# CAN.net
KiCad netlist of a schematic drawn in Altium Designer
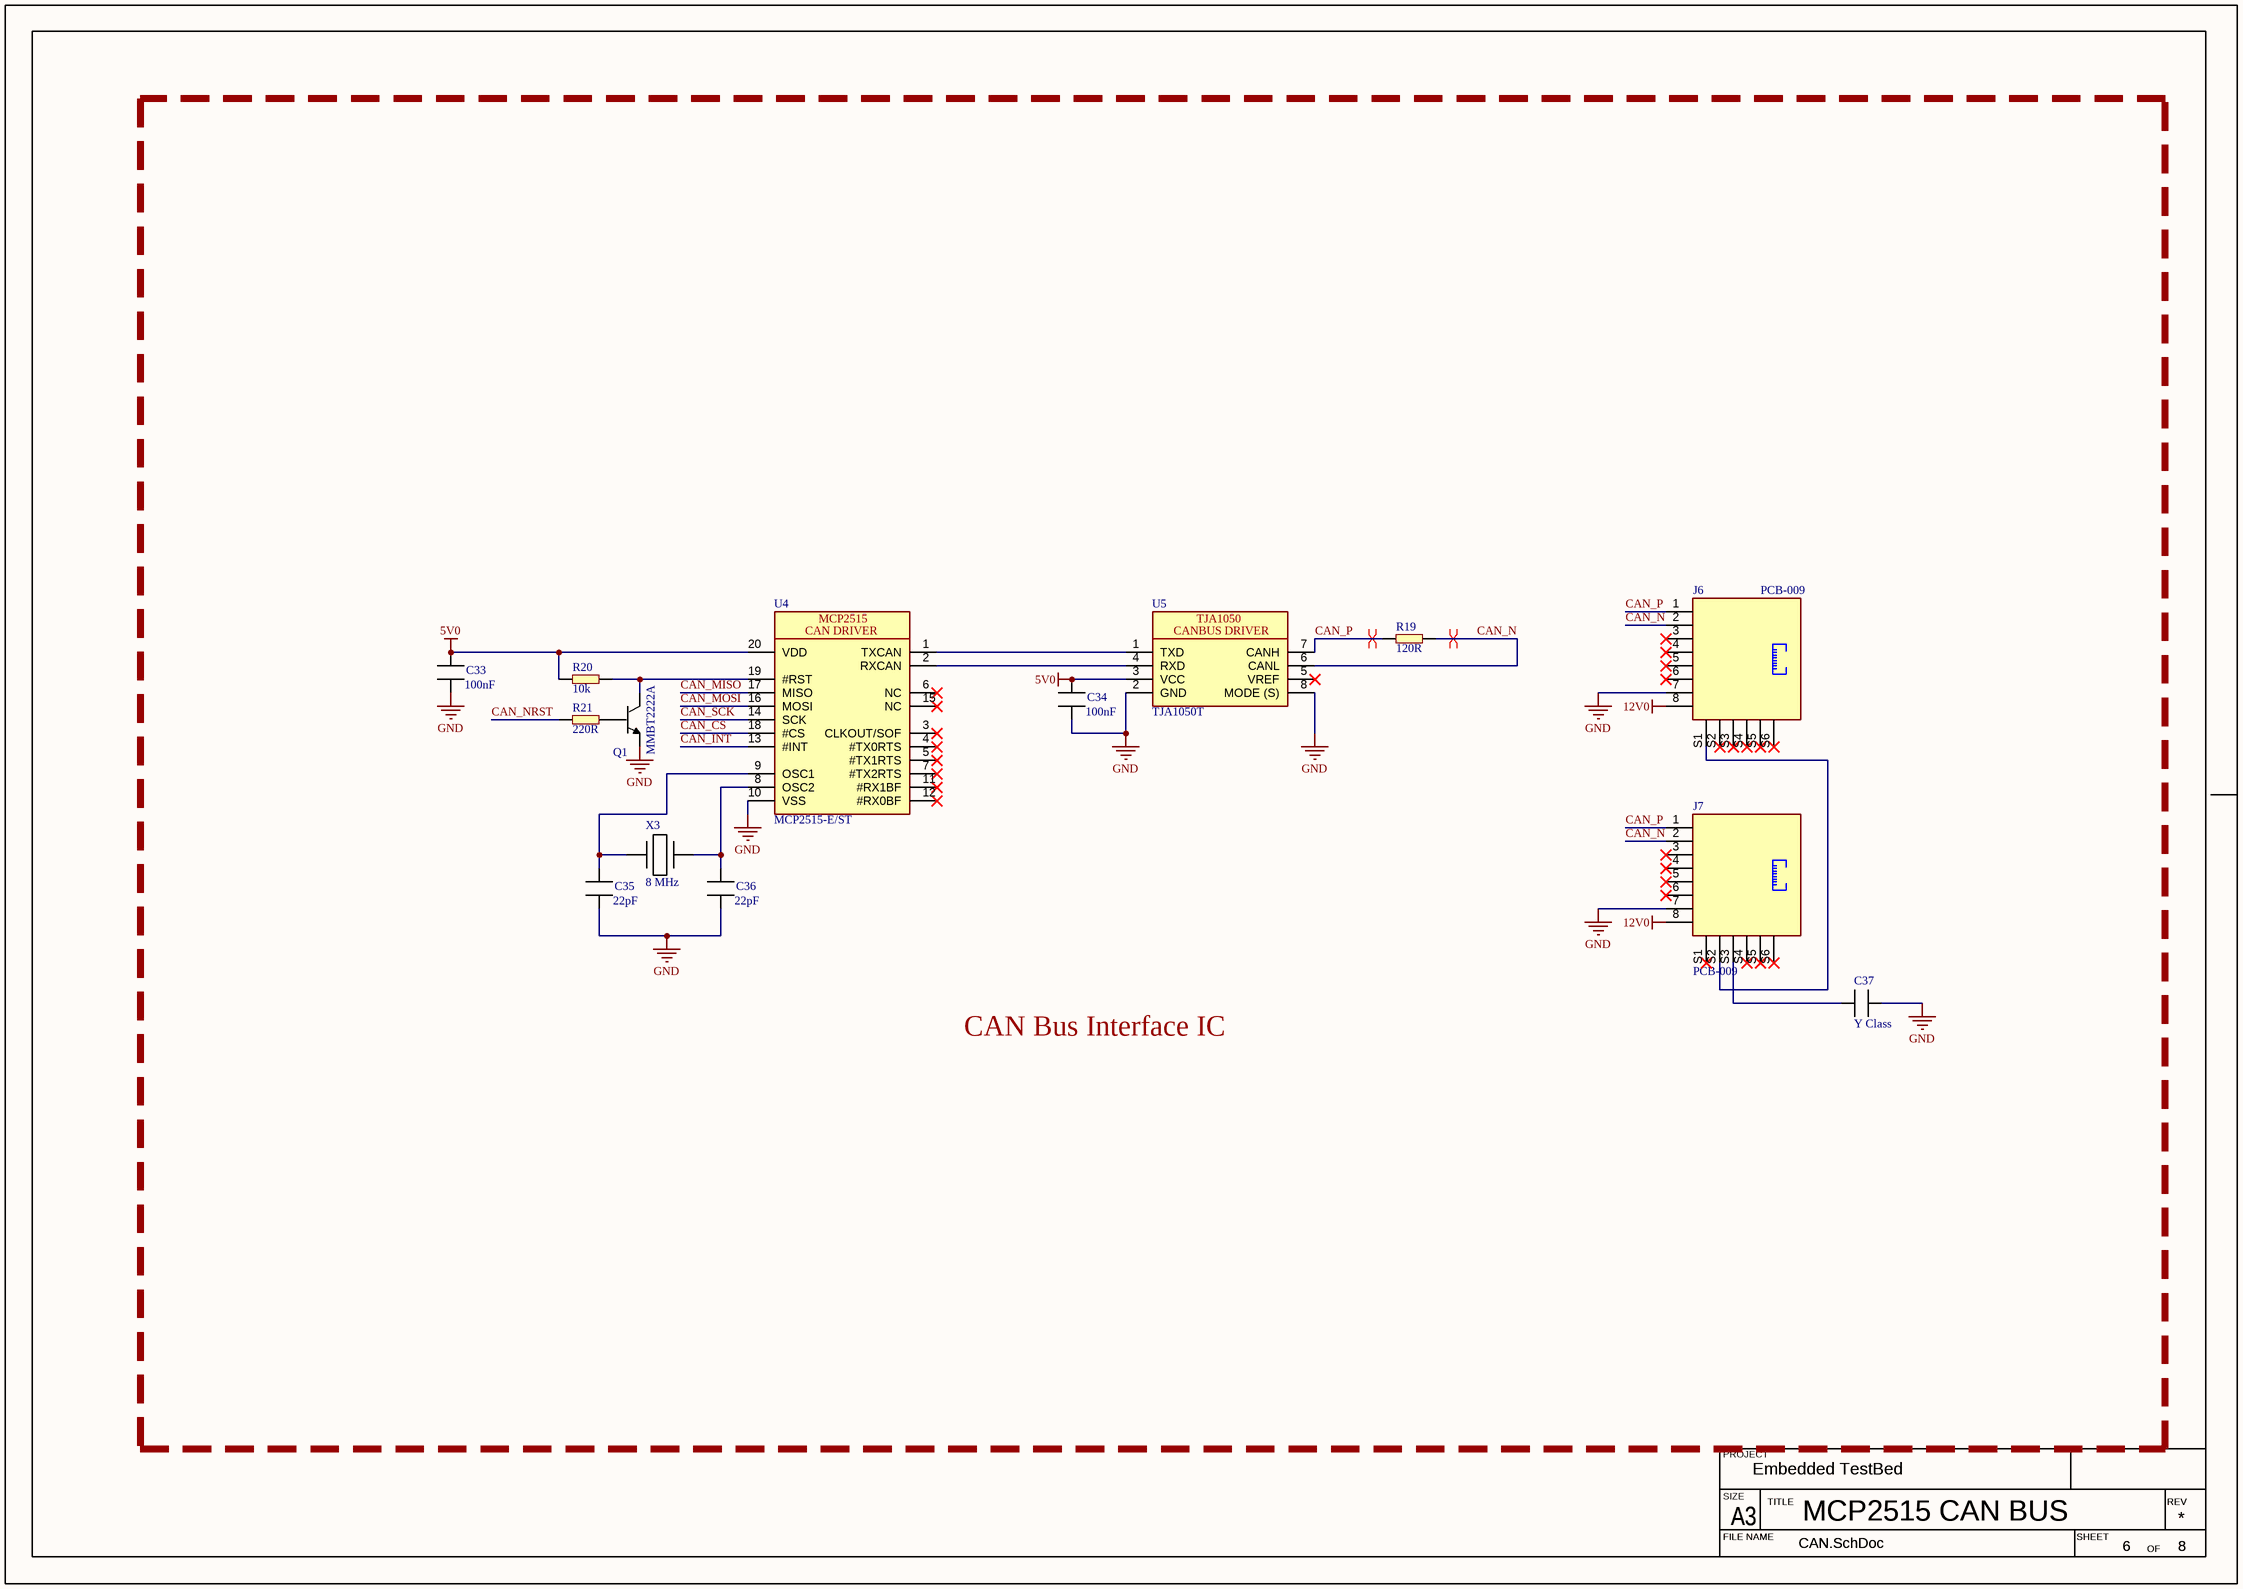
[diagram p0: CAN.SchDoc]

(export (version "E")
  (design (tool "Eeschema 10.0.6"))
  (components
    (comp (ref "C33")
      (value "100nF")
      (footprint "CAPC2012X13L")
      (description "Chip Capacitor, 2-Leads, Body 2.00x1.25mm, IPC High Density")
      (fields (field (name "Comment") "MLCC_0805"))
      (libsource (lib "Capacitor") (part "MLCC_0805"))
    )
    (comp (ref "C34")
      (value "100nF")
      (footprint "CAPC2012X13L")
      (description "Chip Capacitor, 2-Leads, Body 2.00x1.25mm, IPC High Density")
      (fields (field (name "Comment") "MLCC_0805"))
      (libsource (lib "Capacitor") (part "MLCC_0805"))
    )
    (comp (ref "C35")
      (value "22pF")
      (footprint "CAPC2012X13L")
      (description "Chip Capacitor, 2-Leads, Body 2.00x1.25mm, IPC High Density")
      (fields (field (name "Comment") "MLCC_0805"))
      (libsource (lib "Capacitor") (part "MLCC_0805"))
    )
    (comp (ref "C36")
      (value "22pF")
      (footprint "CAPC2012X13L")
      (description "Chip Capacitor, 2-Leads, Body 2.00x1.25mm, IPC High Density")
      (fields (field (name "Comment") "MLCC_0805"))
      (libsource (lib "Capacitor") (part "MLCC_0805"))
    )
    (comp (ref "C37")
      (value "Y Class")
      (footprint "VY1222M43Y5UC63V0")
      (description "Ceramic Capacitor Y5U (E) Radial, Disc")
      (fields (field (name "Comment") "VY1"))
      (libsource (lib "Capacitor") (part "VY1"))
    )
    (comp (ref "J6")
      (value "PCB-009")
      (footprint "PCB-009")
      (description "PCB-009 Robu")
      (fields (field (name "Comment") "ERP_148-3"))
      (libsource (lib "Connectors") (part "RJ45_Top_Entry"))
    )
    (comp (ref "J7")
      (value "PCB-009")
      (footprint "PCB-009")
      (description "PCB-009 Robu")
      (fields (field (name "Comment") "ERP_148-3"))
      (libsource (lib "Connectors") (part "RJ45_Top_Entry"))
    )
    (comp (ref "Q1")
      (value "MMBT2222A")
      (footprint "MMBT2222")
      (fields (field (name "Comment") "ERP_105-1"))
      (libsource (lib "BJT") (part "MMBT2222"))
    )
    (comp (ref "R19")
      (value "120R")
      (footprint "RES_0603")
      (description "RES_0603")
      (fields (field (name "Comment") "ERP_101-1"))
      (libsource (lib "Resistor") (part "RES_0603"))
    )
    (comp (ref "R20")
      (value "10k")
      (footprint "RES_0603")
      (description "RES_0603")
      (fields (field (name "Comment") "ERP_101-1"))
      (libsource (lib "Resistor") (part "RES_0603"))
    )
    (comp (ref "R21")
      (value "220R")
      (footprint "RES_0603")
      (description "RES_0603")
      (fields (field (name "Comment") "ERP_101-1"))
      (libsource (lib "Resistor") (part "RES_0603"))
    )
    (comp (ref "U4")
      (value "MCP2515-E/ST")
      (footprint "MCP2515-ST")
      (description "CAN Interface IC")
      (fields (field (name "Comment") "MCP2515"))
      (libsource (lib "Communication") (part "MCP2515"))
    )
    (comp (ref "U5")
      (value "TJA1050T")
      (footprint "TJA1050T")
      (description "CAN Transceiver IC")
      (fields (field (name "Comment") "TJA1050"))
      (libsource (lib "Communication") (part "TJA1050"))
    )
    (comp (ref "X3")
      (value "8 MHz")
      (footprint "HC-49US")
      (description "CRYSTAL HC-49US 2 Pin")
      (fields (field (name "Comment") "HC-49US"))
      (libsource (lib "Crystal") (part "HC-49US"))
    )
  )
  (nets
    (net (code "1") (name "/CAN_CS") (class "Default")
      (node (ref "U4") (pin "18") (pinfunction "#CS_18") (pintype "passive"))
    )
    (net (code "2") (name "/CAN_INT") (class "Default")
      (node (ref "U4") (pin "13") (pinfunction "#INT_13") (pintype "passive"))
    )
    (net (code "3") (name "/CAN_MISO") (class "Default")
      (node (ref "U4") (pin "17") (pinfunction "MISO_17") (pintype "passive"))
    )
    (net (code "4") (name "/CAN_MOSI") (class "Default")
      (node (ref "U4") (pin "16") (pinfunction "MOSI_16") (pintype "passive"))
    )
    (net (code "5") (name "/CAN_N") (class "Default")
      (node (ref "J6") (pin "2") (pinfunction "2_2") (pintype "passive"))
      (node (ref "J7") (pin "2") (pinfunction "2_2") (pintype "passive"))
      (node (ref "R19") (pin "2") (pinfunction "2_2") (pintype "passive"))
      (node (ref "U5") (pin "6") (pinfunction "CANL_6") (pintype "passive"))
    )
    (net (code "6") (name "/CAN_NRST") (class "Default")
      (node (ref "R21") (pin "1") (pinfunction "1_1") (pintype "passive"))
    )
    (net (code "7") (name "/CAN_P") (class "Default")
      (node (ref "J6") (pin "1") (pinfunction "1_1") (pintype "passive"))
      (node (ref "J7") (pin "1") (pinfunction "1_1") (pintype "passive"))
      (node (ref "R19") (pin "1") (pinfunction "1_1") (pintype "passive"))
      (node (ref "U5") (pin "7") (pinfunction "CANH_7") (pintype "passive"))
    )
    (net (code "8") (name "/CAN_SCK") (class "Default")
      (node (ref "U4") (pin "14") (pinfunction "SCK_14") (pintype "passive"))
    )
    (net (code "9") (name "5V0") (class "Default")
      (node (ref "C33") (pin "1") (pinfunction "1_1") (pintype "passive"))
      (node (ref "C34") (pin "1") (pinfunction "1_1") (pintype "passive"))
      (node (ref "R20") (pin "1") (pinfunction "1_1") (pintype "passive"))
      (node (ref "U4") (pin "20") (pinfunction "VDD_20") (pintype "passive"))
      (node (ref "U5") (pin "3") (pinfunction "VCC_3") (pintype "passive"))
    )
    (net (code "10") (name "12V0") (class "Default")
      (node (ref "J6") (pin "8") (pinfunction "8_8") (pintype "passive"))
      (node (ref "J7") (pin "8") (pinfunction "8_8") (pintype "passive"))
    )
    (net (code "11") (name "GND") (class "Default")
      (node (ref "C33") (pin "2") (pinfunction "2_2") (pintype "passive"))
      (node (ref "C34") (pin "2") (pinfunction "2_2") (pintype "passive"))
      (node (ref "C35") (pin "2") (pinfunction "2_2") (pintype "passive"))
      (node (ref "C36") (pin "2") (pinfunction "2_2") (pintype "passive"))
      (node (ref "C37") (pin "2") (pinfunction "2_2") (pintype "passive"))
      (node (ref "J6") (pin "7") (pinfunction "7_7") (pintype "passive"))
      (node (ref "J7") (pin "7") (pinfunction "7_7") (pintype "passive"))
      (node (ref "Q1") (pin "2") (pinfunction "2_2") (pintype "passive"))
      (node (ref "U4") (pin "10") (pinfunction "VSS_10") (pintype "passive"))
      (node (ref "U5") (pin "2") (pinfunction "GND_2") (pintype "passive"))
      (node (ref "U5") (pin "8") (pinfunction "MODE_(S)_8") (pintype "passive"))
    )
    (net (code "12") (name "Net-(C37-Pad1)") (class "Default")
      (node (ref "C37") (pin "1") (pinfunction "1_1") (pintype "passive"))
      (node (ref "J7") (pin "S3") (pinfunction "S3_S3") (pintype "passive"))
    )
    (net (code "13") (name "Net-(J6-PadS1)") (class "Default")
      (node (ref "J6") (pin "S1") (pinfunction "S1_S1") (pintype "passive"))
      (node (ref "J7") (pin "S2") (pinfunction "S2_S2") (pintype "passive"))
    )
    (net (code "14") (name "Net-(Q1-Pad1)") (class "Default")
      (node (ref "Q1") (pin "1") (pinfunction "1_1") (pintype "passive"))
      (node (ref "R21") (pin "2") (pinfunction "2_2") (pintype "passive"))
    )
    (net (code "15") (name "Net-(U4-#RST)") (class "Default")
      (node (ref "Q1") (pin "3") (pinfunction "3_3") (pintype "passive"))
      (node (ref "R20") (pin "2") (pinfunction "2_2") (pintype "passive"))
      (node (ref "U4") (pin "19") (pinfunction "#RST_19") (pintype "passive"))
    )
    (net (code "16") (name "Net-(U4-OSC1)") (class "Default")
      (node (ref "C35") (pin "1") (pinfunction "1_1") (pintype "passive"))
      (node (ref "U4") (pin "9") (pinfunction "OSC1_9") (pintype "passive"))
      (node (ref "X3") (pin "1") (pinfunction "1_1") (pintype "passive"))
    )
    (net (code "17") (name "Net-(U4-OSC2)") (class "Default")
      (node (ref "C36") (pin "1") (pinfunction "1_1") (pintype "passive"))
      (node (ref "U4") (pin "8") (pinfunction "OSC2_8") (pintype "passive"))
      (node (ref "X3") (pin "2") (pinfunction "2_2") (pintype "passive"))
    )
    (net (code "18") (name "Net-(U4-RXCAN)") (class "Default")
      (node (ref "U4") (pin "2") (pinfunction "RXCAN_2") (pintype "passive"))
      (node (ref "U5") (pin "4") (pinfunction "RXD_4") (pintype "passive"))
    )
    (net (code "19") (name "Net-(U4-TXCAN)") (class "Default")
      (node (ref "U4") (pin "1") (pinfunction "TXCAN_1") (pintype "passive"))
      (node (ref "U5") (pin "1") (pinfunction "TXD_1") (pintype "passive"))
    )
    (net (code "20") (name "unconnected-(J6-Pad3)") (class "Default")
      (node (ref "J6") (pin "3") (pinfunction "3_3") (pintype "passive+no_connect"))
    )
    (net (code "21") (name "unconnected-(J6-Pad4)") (class "Default")
      (node (ref "J6") (pin "4") (pinfunction "4_4") (pintype "passive+no_connect"))
    )
    (net (code "22") (name "unconnected-(J6-Pad5)") (class "Default")
      (node (ref "J6") (pin "5") (pinfunction "5_5") (pintype "passive+no_connect"))
    )
    (net (code "23") (name "unconnected-(J6-Pad6)") (class "Default")
      (node (ref "J6") (pin "6") (pinfunction "6_6") (pintype "passive+no_connect"))
    )
    (net (code "24") (name "unconnected-(J6-PadS2)") (class "Default")
      (node (ref "J6") (pin "S2") (pinfunction "S2_S2") (pintype "passive+no_connect"))
    )
    (net (code "25") (name "unconnected-(J6-PadS3)") (class "Default")
      (node (ref "J6") (pin "S3") (pinfunction "S3_S3") (pintype "passive+no_connect"))
    )
    (net (code "26") (name "unconnected-(J6-PadS4)") (class "Default")
      (node (ref "J6") (pin "S4") (pinfunction "S4_S4") (pintype "passive+no_connect"))
    )
    (net (code "27") (name "unconnected-(J6-PadS5)") (class "Default")
      (node (ref "J6") (pin "S5") (pinfunction "S5_S5") (pintype "passive+no_connect"))
    )
    (net (code "28") (name "unconnected-(J6-PadS6)") (class "Default")
      (node (ref "J6") (pin "S6") (pinfunction "S6_S6") (pintype "passive+no_connect"))
    )
    (net (code "29") (name "unconnected-(J7-Pad3)") (class "Default")
      (node (ref "J7") (pin "3") (pinfunction "3_3") (pintype "passive+no_connect"))
    )
    (net (code "30") (name "unconnected-(J7-Pad4)") (class "Default")
      (node (ref "J7") (pin "4") (pinfunction "4_4") (pintype "passive+no_connect"))
    )
    (net (code "31") (name "unconnected-(J7-Pad5)") (class "Default")
      (node (ref "J7") (pin "5") (pinfunction "5_5") (pintype "passive+no_connect"))
    )
    (net (code "32") (name "unconnected-(J7-Pad6)") (class "Default")
      (node (ref "J7") (pin "6") (pinfunction "6_6") (pintype "passive+no_connect"))
    )
    (net (code "33") (name "unconnected-(J7-PadS1)") (class "Default")
      (node (ref "J7") (pin "S1") (pinfunction "S1_S1") (pintype "passive+no_connect"))
    )
    (net (code "34") (name "unconnected-(J7-PadS4)") (class "Default")
      (node (ref "J7") (pin "S4") (pinfunction "S4_S4") (pintype "passive+no_connect"))
    )
    (net (code "35") (name "unconnected-(J7-PadS5)") (class "Default")
      (node (ref "J7") (pin "S5") (pinfunction "S5_S5") (pintype "passive+no_connect"))
    )
    (net (code "36") (name "unconnected-(J7-PadS6)") (class "Default")
      (node (ref "J7") (pin "S6") (pinfunction "S6_S6") (pintype "passive+no_connect"))
    )
    (net (code "37") (name "unconnected-(U4-#RX0BF-Pad12)") (class "Default")
      (node (ref "U4") (pin "12") (pinfunction "#RX0BF_12") (pintype "passive+no_connect"))
    )
    (net (code "38") (name "unconnected-(U4-#RX1BF-Pad11)") (class "Default")
      (node (ref "U4") (pin "11") (pinfunction "#RX1BF_11") (pintype "passive+no_connect"))
    )
    (net (code "39") (name "unconnected-(U4-#TX0RTS-Pad4)") (class "Default")
      (node (ref "U4") (pin "4") (pinfunction "#TX0RTS_4") (pintype "passive+no_connect"))
    )
    (net (code "40") (name "unconnected-(U4-#TX1RTS-Pad5)") (class "Default")
      (node (ref "U4") (pin "5") (pinfunction "#TX1RTS_5") (pintype "passive+no_connect"))
    )
    (net (code "41") (name "unconnected-(U4-#TX2RTS-Pad7)") (class "Default")
      (node (ref "U4") (pin "7") (pinfunction "#TX2RTS_7") (pintype "passive+no_connect"))
    )
    (net (code "42") (name "unconnected-(U4-CLKOUT{slash}SOF-Pad3)") (class "Default")
      (node (ref "U4") (pin "3") (pinfunction "CLKOUT/SOF_3") (pintype "passive+no_connect"))
    )
    (net (code "43") (name "unconnected-(U4-NC-Pad6)") (class "Default")
      (node (ref "U4") (pin "6") (pinfunction "NC_6") (pintype "passive+no_connect"))
    )
    (net (code "44") (name "unconnected-(U4-NC-Pad15)") (class "Default")
      (node (ref "U4") (pin "15") (pinfunction "NC_15") (pintype "passive+no_connect"))
    )
    (net (code "45") (name "unconnected-(U5-VREF-Pad5)") (class "Default")
      (node (ref "U5") (pin "5") (pinfunction "VREF_5") (pintype "passive+no_connect"))
    )
  )
)
